# uINS.net
KiCad netlist of a schematic drawn in Altium Designer
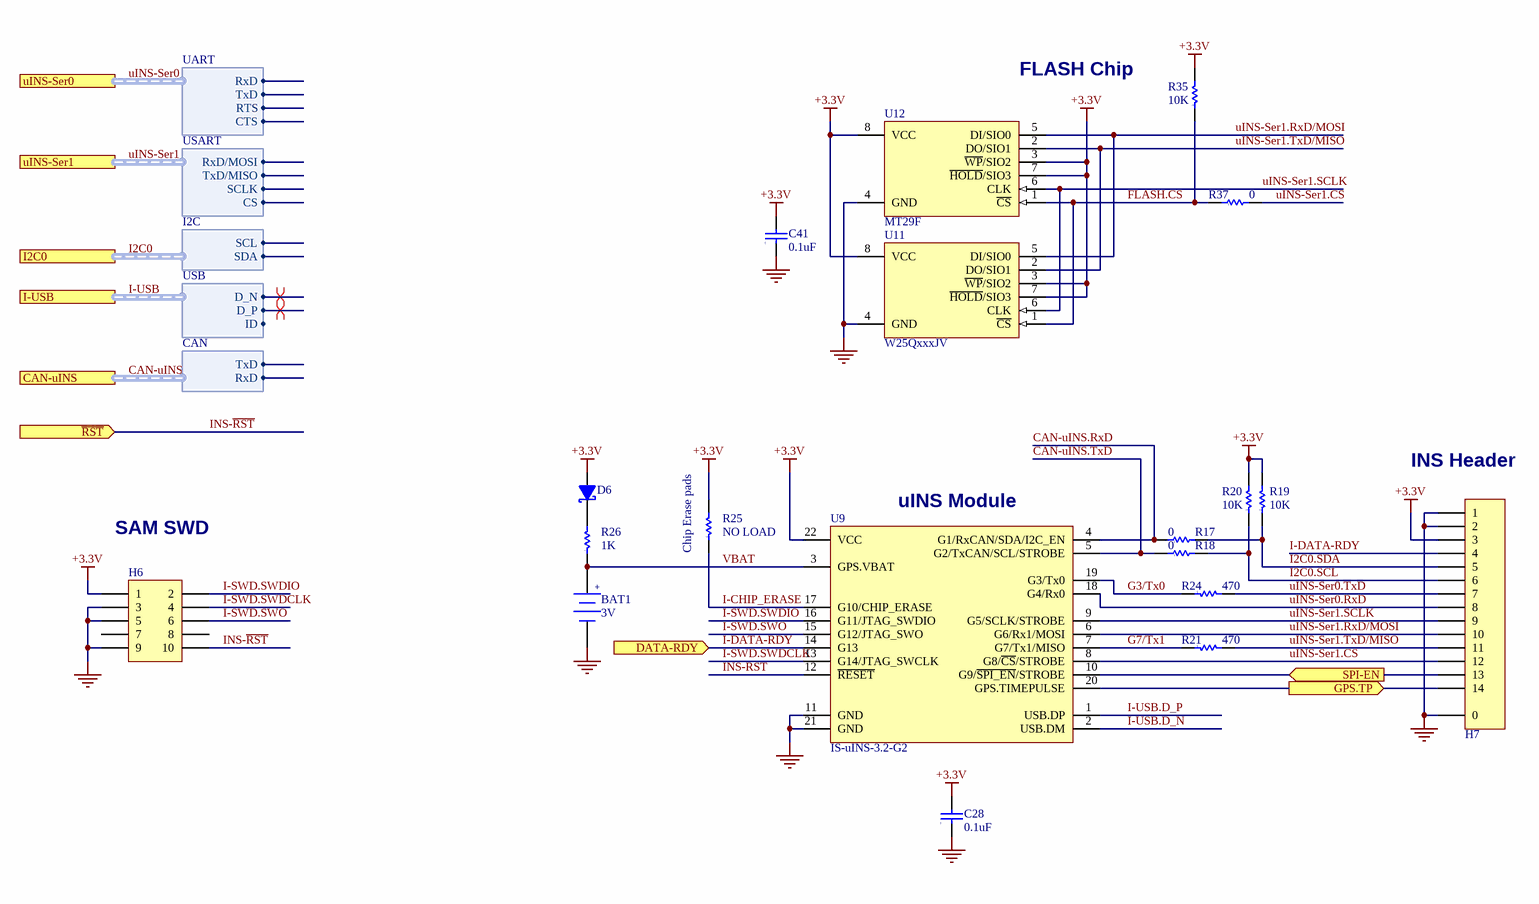
[diagram p0: uINS.SchDoc]

(export (version "E")
  (design (tool "Eeschema 10.0.6"))
  (components
    (comp (ref "BAT1")
      (value "Battery")
      (footprint "ML614S")
      (description "BATTERY LITH 3V RECHARGE SMD")
      (fields
        (field (name "MANUFACTURER") "Seiko")
        (field (name "MANUFACTURER PART NUMBER") "MS621T-FL11E")
        (field (name "VOLTAGE RATING") "3V")
      )
      (libsource (lib "General") (part "Battery"))
    )
    (comp (ref "C28")
      (value "0.1uF")
      (footprint "0402")
      (description "CAP CER .10UF 50V X7R 10% 0402")
      (fields
        (field (name "MANUFACTURER") "TDK Corporation")
        (field (name "MANUFACTURER PART NUMBER") "C1005X7R1H104K")
        (field (name "PUBLISHER") "Altium Limited")
      )
      (libsource (lib "General") (part "Cap"))
    )
    (comp (ref "C41")
      (value "0.1uF")
      (footprint "0402")
      (description "CAP CER .10UF 50V X7R 10% 0402")
      (fields
        (field (name "MANUFACTURER") "TDK Corporation")
        (field (name "MANUFACTURER PART NUMBER") "C1005X7R1H104K")
        (field (name "PUBLISHER") "Altium Limited")
      )
      (libsource (lib "General") (part "Cap"))
    )
    (comp (ref "D6")
      (value "Diode - Schottky")
      (footprint "D0603B")
      (description "DIODE SCHOTTKY 30V 2A 0603")
      (fields
        (field (name "MANUFACTURER") "Vishay")
        (field (name "MANUFACTURER PART NUMBER") "VSKY20301608-G4-08")
      )
      (libsource (lib "General") (part "Diode - Schottky"))
    )
    (comp (ref "H6")
      (value "Hdr - 5x2pin")
      (footprint "FTSH-105-01-L-DV-K-A-P")
      (description "CONN HEADER 10POS DUAL .05\" SMD")
      (fields
        (field (name "MANUFACTURER") "Samtec")
        (field (name "MANUFACTURER PART NUMBER") "FTSH-105-01-L-DV-K-A-P")
      )
      (libsource (lib "Connectors") (part "Hdr - 5x2pin"))
    )
    (comp (ref "H7")
      (value "Hdr - 14pin - mount")
      (footprint "SM14B-GHS-TB(LF)(SN)")
      (description "CONN HEADER GH SIDE 14POS 1.25MM")
      (fields
        (field (name "MANUFACTURER") "JST")
        (field (name "MANUFACTURER PART NUMBER") "SM14B-GHS-TB(LF)(SN)")
      )
      (libsource (lib "Connectors") (part "Hdr - 14pin - mount"))
    )
    (comp (ref "R17")
      (value "0")
      (footprint "R0402")
      (description "RES SMD 0 OHM JUMPER 1/16W 0402")
      (fields
        (field (name "MANUFACTURER") "Yageo")
        (field (name "MANUFACTURER PART NUMBER") "RC0402JR-070RL")
      )
      (libsource (lib "") (part "Res_2"))
    )
    (comp (ref "R18")
      (value "0")
      (footprint "R0402")
      (description "RES SMD 0 OHM JUMPER 1/16W 0402")
      (fields
        (field (name "MANUFACTURER") "Yageo")
        (field (name "MANUFACTURER PART NUMBER") "RC0402JR-070RL")
      )
      (libsource (lib "") (part "Res_2"))
    )
    (comp (ref "R19")
      (value "10K")
      (footprint "R0402")
      (description "RES 10K OHM 1/16W 1% 0402 SMD")
      (fields
        (field (name "MANUFACTURER") "Panasonic")
        (field (name "MANUFACTURER PART NUMBER") "ERJ-2RKF1002X")
      )
      (libsource (lib "") (part "Res_1"))
    )
    (comp (ref "R20")
      (value "10K")
      (footprint "R0402")
      (description "RES 10K OHM 1/16W 1% 0402 SMD")
      (fields
        (field (name "MANUFACTURER") "Panasonic")
        (field (name "MANUFACTURER PART NUMBER") "ERJ-2RKF1002X")
      )
      (libsource (lib "") (part "Res_1"))
    )
    (comp (ref "R21")
      (value "470")
      (footprint "R0402")
      (description "RES 470 OHM 1/16W 1% 0402 SMD")
      (fields
        (field (name "MANUFACTURER") "Vishay Dale")
        (field (name "MANUFACTURER PART NUMBER") "CRCW0402470RFKED")
      )
      (libsource (lib "General") (part "Res"))
    )
    (comp (ref "R24")
      (value "470")
      (footprint "R0402")
      (description "RES 470 OHM 1/16W 1% 0402 SMD")
      (fields
        (field (name "MANUFACTURER") "Vishay Dale")
        (field (name "MANUFACTURER PART NUMBER") "CRCW0402470RFKED")
      )
      (libsource (lib "General") (part "Res"))
    )
    (comp (ref "R25")
      (value "NO LOAD")
      (footprint "R0402")
      (description "RES 1.00K OHM 1/16W 1% 0402 SMD")
      (fields (field (name "Comment") "Res"))
      (libsource (lib "") (part "Res_1"))
    )
    (comp (ref "R26")
      (value "1K")
      (footprint "R0402")
      (description "RES 1.00K OHM 1/16W 1% 0402 SMD")
      (fields
        (field (name "MANUFACTURER") "Yageo")
        (field (name "MANUFACTURER PART NUMBER") "RC0402FR-071KL")
      )
      (libsource (lib "") (part "Res_1"))
    )
    (comp (ref "R35")
      (value "10K")
      (footprint "R0402")
      (description "RES 10K OHM 1/16W 1% 0402 SMD")
      (fields
        (field (name "MANUFACTURER") "Panasonic")
        (field (name "MANUFACTURER PART NUMBER") "ERJ-2RKF1002X")
      )
      (libsource (lib "") (part "Res_1"))
    )
    (comp (ref "R37")
      (value "0")
      (footprint "R0402")
      (description "RES SMD 0 OHM JUMPER 1/16W 0402")
      (fields
        (field (name "MANUFACTURER") "Yageo")
        (field (name "MANUFACTURER PART NUMBER") "RC0402JR-070RL")
      )
      (libsource (lib "") (part "Res_2"))
    )
    (comp (ref "U9")
      (value "uINS")
      (footprint "IS-uINS-3.2_no_paste")
      (description "Inertial Sense uINS")
      (fields
        (field (name "MANUFACTURER") "Inertial Sense")
        (field (name "MANUFACTURER PART NUMBER") "IS-uINS-3.2-G2")
      )
      (libsource (lib "InertialSense") (part "IS-uINS-3.2"))
    )
    (comp (ref "U11")
      (value "W25QxxxJV")
      (footprint "SOIC127P790X216-8N")
      (description "IC FLASH 128M SPI 133MHZ 8SOIC")
      (fields
        (field (name "MANUFACTURER") "Winbond")
        (field (name "MANUFACTURER PART NUMBER") "W25Q128JVSIQTR")
      )
      (libsource (lib "ICs") (part "W25Q128JV"))
    )
    (comp (ref "U12")
      (value "MT29F")
      (footprint "DFN800X600X65-8N")
      (description "IC FLASH 1G/2G SPI 8UPDFN")
      (fields
        (field (name "MANUFACTURER") "Micron Technology")
        (field (name "MANUFACTURER PART NUMBER") "MT29F2G01ABAGDWB-IT:GTR")
      )
      (libsource (lib "ICs") (part "MT29F"))
    )
  )
  (nets
    (net (code "6") (name "+3.3V") (class "Default")
      (node (ref "C28") (pin "2") (pinfunction "2_2") (pintype "passive"))
      (node (ref "C41") (pin "2") (pinfunction "2_2") (pintype "passive"))
      (node (ref "D6") (pin "A") (pinfunction "A_A") (pintype "passive"))
      (node (ref "H6") (pin "1") (pinfunction "1_1") (pintype "passive"))
      (node (ref "H7") (pin "3") (pinfunction "3_3") (pintype "passive"))
      (node (ref "R19") (pin "2") (pinfunction "2_2") (pintype "passive"))
      (node (ref "R20") (pin "2") (pinfunction "2_2") (pintype "passive"))
      (node (ref "R25") (pin "2") (pinfunction "2_2") (pintype "passive"))
      (node (ref "R35") (pin "2") (pinfunction "2_2") (pintype "passive"))
      (node (ref "U11") (pin "3") (pinfunction "~{WP}/SIO2_3") (pintype "passive"))
      (node (ref "U11") (pin "7") (pinfunction "~{HOLD}/SIO3_7") (pintype "passive"))
      (node (ref "U11") (pin "8") (pinfunction "VCC_8") (pintype "power_in"))
      (node (ref "U12") (pin "3") (pinfunction "~{WP}/SIO2_3") (pintype "passive"))
      (node (ref "U12") (pin "7") (pinfunction "~{HOLD}/SIO3_7") (pintype "passive"))
      (node (ref "U12") (pin "8") (pinfunction "VCC_8") (pintype "power_in"))
      (node (ref "U9") (pin "22") (pinfunction "VCC_22") (pintype "power_in"))
    )
    (net (code "7") (name "/CAN-uINS.RxD") (class "Default")
      (node (ref "R17") (pin "1") (pinfunction "1_1") (pintype "passive"))
      (node (ref "U9") (pin "4") (pinfunction "G1/RxCAN/SDA/I2C_EN_4") (pintype "passive"))
    )
    (net (code "8") (name "/CAN-uINS.TxD") (class "Default")
      (node (ref "R18") (pin "1") (pinfunction "1_1") (pintype "passive"))
      (node (ref "U9") (pin "5") (pinfunction "G2/TxCAN/SCL/STROBE_5") (pintype "passive"))
    )
    (net (code "10") (name "/FLASH.CS") (class "Default")
      (node (ref "R35") (pin "1") (pinfunction "1_1") (pintype "passive"))
      (node (ref "R37") (pin "1") (pinfunction "1_1") (pintype "passive"))
      (node (ref "U11") (pin "1") (pinfunction "CS_1") (pintype "input"))
      (node (ref "U12") (pin "1") (pinfunction "CS_1") (pintype "input"))
    )
    (net (code "11") (name "/G3{slash}Tx0") (class "Default")
      (node (ref "R24") (pin "1") (pinfunction "1_1") (pintype "passive"))
      (node (ref "U9") (pin "19") (pinfunction "G3/Tx0_19") (pintype "passive"))
    )
    (net (code "12") (name "/G7{slash}Tx1") (class "Default")
      (node (ref "R21") (pin "1") (pinfunction "1_1") (pintype "passive"))
      (node (ref "U9") (pin "7") (pinfunction "G7/Tx1/MISO_7") (pintype "passive"))
    )
    (net (code "13") (name "/GPS.TP") (class "Default")
      (node (ref "H7") (pin "14") (pinfunction "14_14") (pintype "passive"))
      (node (ref "U9") (pin "20") (pinfunction "GPS.TIMEPULSE_20") (pintype "passive"))
    )
    (net (code "14") (name "/I-CHIP_ERASE") (class "Default")
      (node (ref "R25") (pin "1") (pinfunction "1_1") (pintype "passive"))
      (node (ref "U9") (pin "17") (pinfunction "G10/CHIP_ERASE_17") (pintype "passive"))
    )
    (net (code "15") (name "/I-DATA-RDY") (class "Default")
      (node (ref "H7") (pin "4") (pinfunction "4_4") (pintype "passive"))
      (node (ref "U9") (pin "14") (pinfunction "G13_14") (pintype "passive"))
    )
    (net (code "16") (name "/I-SWD.SWDCLK") (class "Default")
      (node (ref "H6") (pin "4") (pinfunction "4_4") (pintype "passive"))
      (node (ref "U9") (pin "13") (pinfunction "G14/JTAG_SWCLK_13") (pintype "passive"))
    )
    (net (code "17") (name "/I-SWD.SWDIO") (class "Default")
      (node (ref "H6") (pin "2") (pinfunction "2_2") (pintype "passive"))
      (node (ref "U9") (pin "16") (pinfunction "G11/JTAG_SWDIO_16") (pintype "passive"))
    )
    (net (code "18") (name "/I-SWD.SWO") (class "Default")
      (node (ref "H6") (pin "6") (pinfunction "6_6") (pintype "passive"))
      (node (ref "U9") (pin "15") (pinfunction "G12/JTAG_SWO_15") (pintype "passive"))
    )
    (net (code "19") (name "/I-USB.D_N") (class "Default")
      (node (ref "U9") (pin "2") (pinfunction "USB.DM_2") (pintype "passive"))
    )
    (net (code "20") (name "/I-USB.D_P") (class "Default")
      (node (ref "U9") (pin "1") (pinfunction "USB.DP_1") (pintype "passive"))
    )
    (net (code "22") (name "/I2C0.SCL") (class "Default")
      (node (ref "H7") (pin "6") (pinfunction "6_6") (pintype "passive"))
      (node (ref "R18") (pin "2") (pinfunction "2_2") (pintype "passive"))
      (node (ref "R20") (pin "1") (pinfunction "1_1") (pintype "passive"))
    )
    (net (code "23") (name "/I2C0.SDA") (class "Default")
      (node (ref "H7") (pin "5") (pinfunction "5_5") (pintype "passive"))
      (node (ref "R17") (pin "2") (pinfunction "2_2") (pintype "passive"))
      (node (ref "R19") (pin "1") (pinfunction "1_1") (pintype "passive"))
    )
    (net (code "25") (name "/INS-~{RST}") (class "Default")
      (node (ref "H6") (pin "10") (pinfunction "10_10") (pintype "passive"))
      (node (ref "U9") (pin "12") (pinfunction "~{RESET}_12") (pintype "passive"))
    )
    (net (code "26") (name "/SPI-EN") (class "Default")
      (node (ref "H7") (pin "13") (pinfunction "13_13") (pintype "passive"))
      (node (ref "U9") (pin "10") (pinfunction "G9/~{SPI_EN}/STROBE_10") (pintype "passive"))
    )
    (net (code "27") (name "/VBAT") (class "Default")
      (node (ref "BAT1") (pin "+") (pinfunction "+_+") (pintype "passive"))
      (node (ref "R26") (pin "1") (pinfunction "1_1") (pintype "passive"))
      (node (ref "U9") (pin "3") (pinfunction "GPS.VBAT_3") (pintype "passive"))
    )
    (net (code "28") (name "/uINS-Ser0.RxD") (class "Default")
      (node (ref "H7") (pin "8") (pinfunction "8_8") (pintype "passive"))
      (node (ref "U9") (pin "18") (pinfunction "G4/Rx0_18") (pintype "passive"))
    )
    (net (code "29") (name "/uINS-Ser0.TxD") (class "Default")
      (node (ref "H7") (pin "7") (pinfunction "7_7") (pintype "passive"))
      (node (ref "R24") (pin "2") (pinfunction "2_2") (pintype "passive"))
    )
    (net (code "31") (name "/uINS-Ser1.CS") (class "Default")
      (node (ref "H7") (pin "12") (pinfunction "12_12") (pintype "passive"))
      (node (ref "R37") (pin "2") (pinfunction "2_2") (pintype "passive"))
      (node (ref "U9") (pin "8") (pinfunction "G8/~{CS}/STROBE_8") (pintype "passive"))
    )
    (net (code "32") (name "/uINS-Ser1.RxD{slash}MOSI") (class "Default")
      (node (ref "H7") (pin "10") (pinfunction "10_10") (pintype "passive"))
      (node (ref "U11") (pin "5") (pinfunction "DI/SIO0_5") (pintype "passive"))
      (node (ref "U12") (pin "5") (pinfunction "DI/SIO0_5") (pintype "passive"))
      (node (ref "U9") (pin "6") (pinfunction "G6/Rx1/MOSI_6") (pintype "passive"))
    )
    (net (code "33") (name "/uINS-Ser1.SCLK") (class "Default")
      (node (ref "H7") (pin "9") (pinfunction "9_9") (pintype "passive"))
      (node (ref "U11") (pin "6") (pinfunction "CLK_6") (pintype "input"))
      (node (ref "U12") (pin "6") (pinfunction "CLK_6") (pintype "input"))
      (node (ref "U9") (pin "9") (pinfunction "G5/SCLK/STROBE_9") (pintype "passive"))
    )
    (net (code "34") (name "/uINS-Ser1.TxD{slash}MISO") (class "Default")
      (node (ref "H7") (pin "11") (pinfunction "11_11") (pintype "passive"))
      (node (ref "R21") (pin "2") (pinfunction "2_2") (pintype "passive"))
      (node (ref "U11") (pin "2") (pinfunction "DO/SIO1_2") (pintype "passive"))
      (node (ref "U12") (pin "2") (pinfunction "DO/SIO1_2") (pintype "passive"))
    )
    (net (code "36") (name "GND") (class "Default")
      (node (ref "BAT1") (pin "-") (pinfunction "-_-") (pintype "passive"))
      (node (ref "C28") (pin "1") (pinfunction "1_1") (pintype "passive"))
      (node (ref "C41") (pin "1") (pinfunction "1_1") (pintype "passive"))
      (node (ref "H6") (pin "3") (pinfunction "3_3") (pintype "passive"))
      (node (ref "H6") (pin "5") (pinfunction "5_5") (pintype "passive"))
      (node (ref "H6") (pin "9") (pinfunction "9_9") (pintype "passive"))
      (node (ref "H7") (pin "0") (pinfunction "0_0") (pintype "passive"))
      (node (ref "H7") (pin "1") (pinfunction "1_1") (pintype "passive"))
      (node (ref "H7") (pin "2") (pinfunction "2_2") (pintype "passive"))
      (node (ref "U11") (pin "4") (pinfunction "GND_4") (pintype "power_in"))
      (node (ref "U12") (pin "4") (pinfunction "GND_4") (pintype "power_in"))
      (node (ref "U9") (pin "11") (pinfunction "GND_11") (pintype "power_in"))
      (node (ref "U9") (pin "21") (pinfunction "GND_21") (pintype "power_in"))
    )
    (net (code "37") (name "Net-(D6-PadC)") (class "Default")
      (node (ref "D6") (pin "C") (pinfunction "C_C") (pintype "passive"))
      (node (ref "R26") (pin "2") (pinfunction "2_2") (pintype "passive"))
    )
    (net (code "38") (name "unconnected-(H6-Pad7)") (class "Default")
      (node (ref "H6") (pin "7") (pinfunction "7_7") (pintype "passive"))
    )
    (net (code "39") (name "unconnected-(H6-Pad8)") (class "Default")
      (node (ref "H6") (pin "8") (pinfunction "8_8") (pintype "passive"))
    )
  )
)
